# mcu_energy.net
KiCad netlist of a schematic drawn in EAGLE
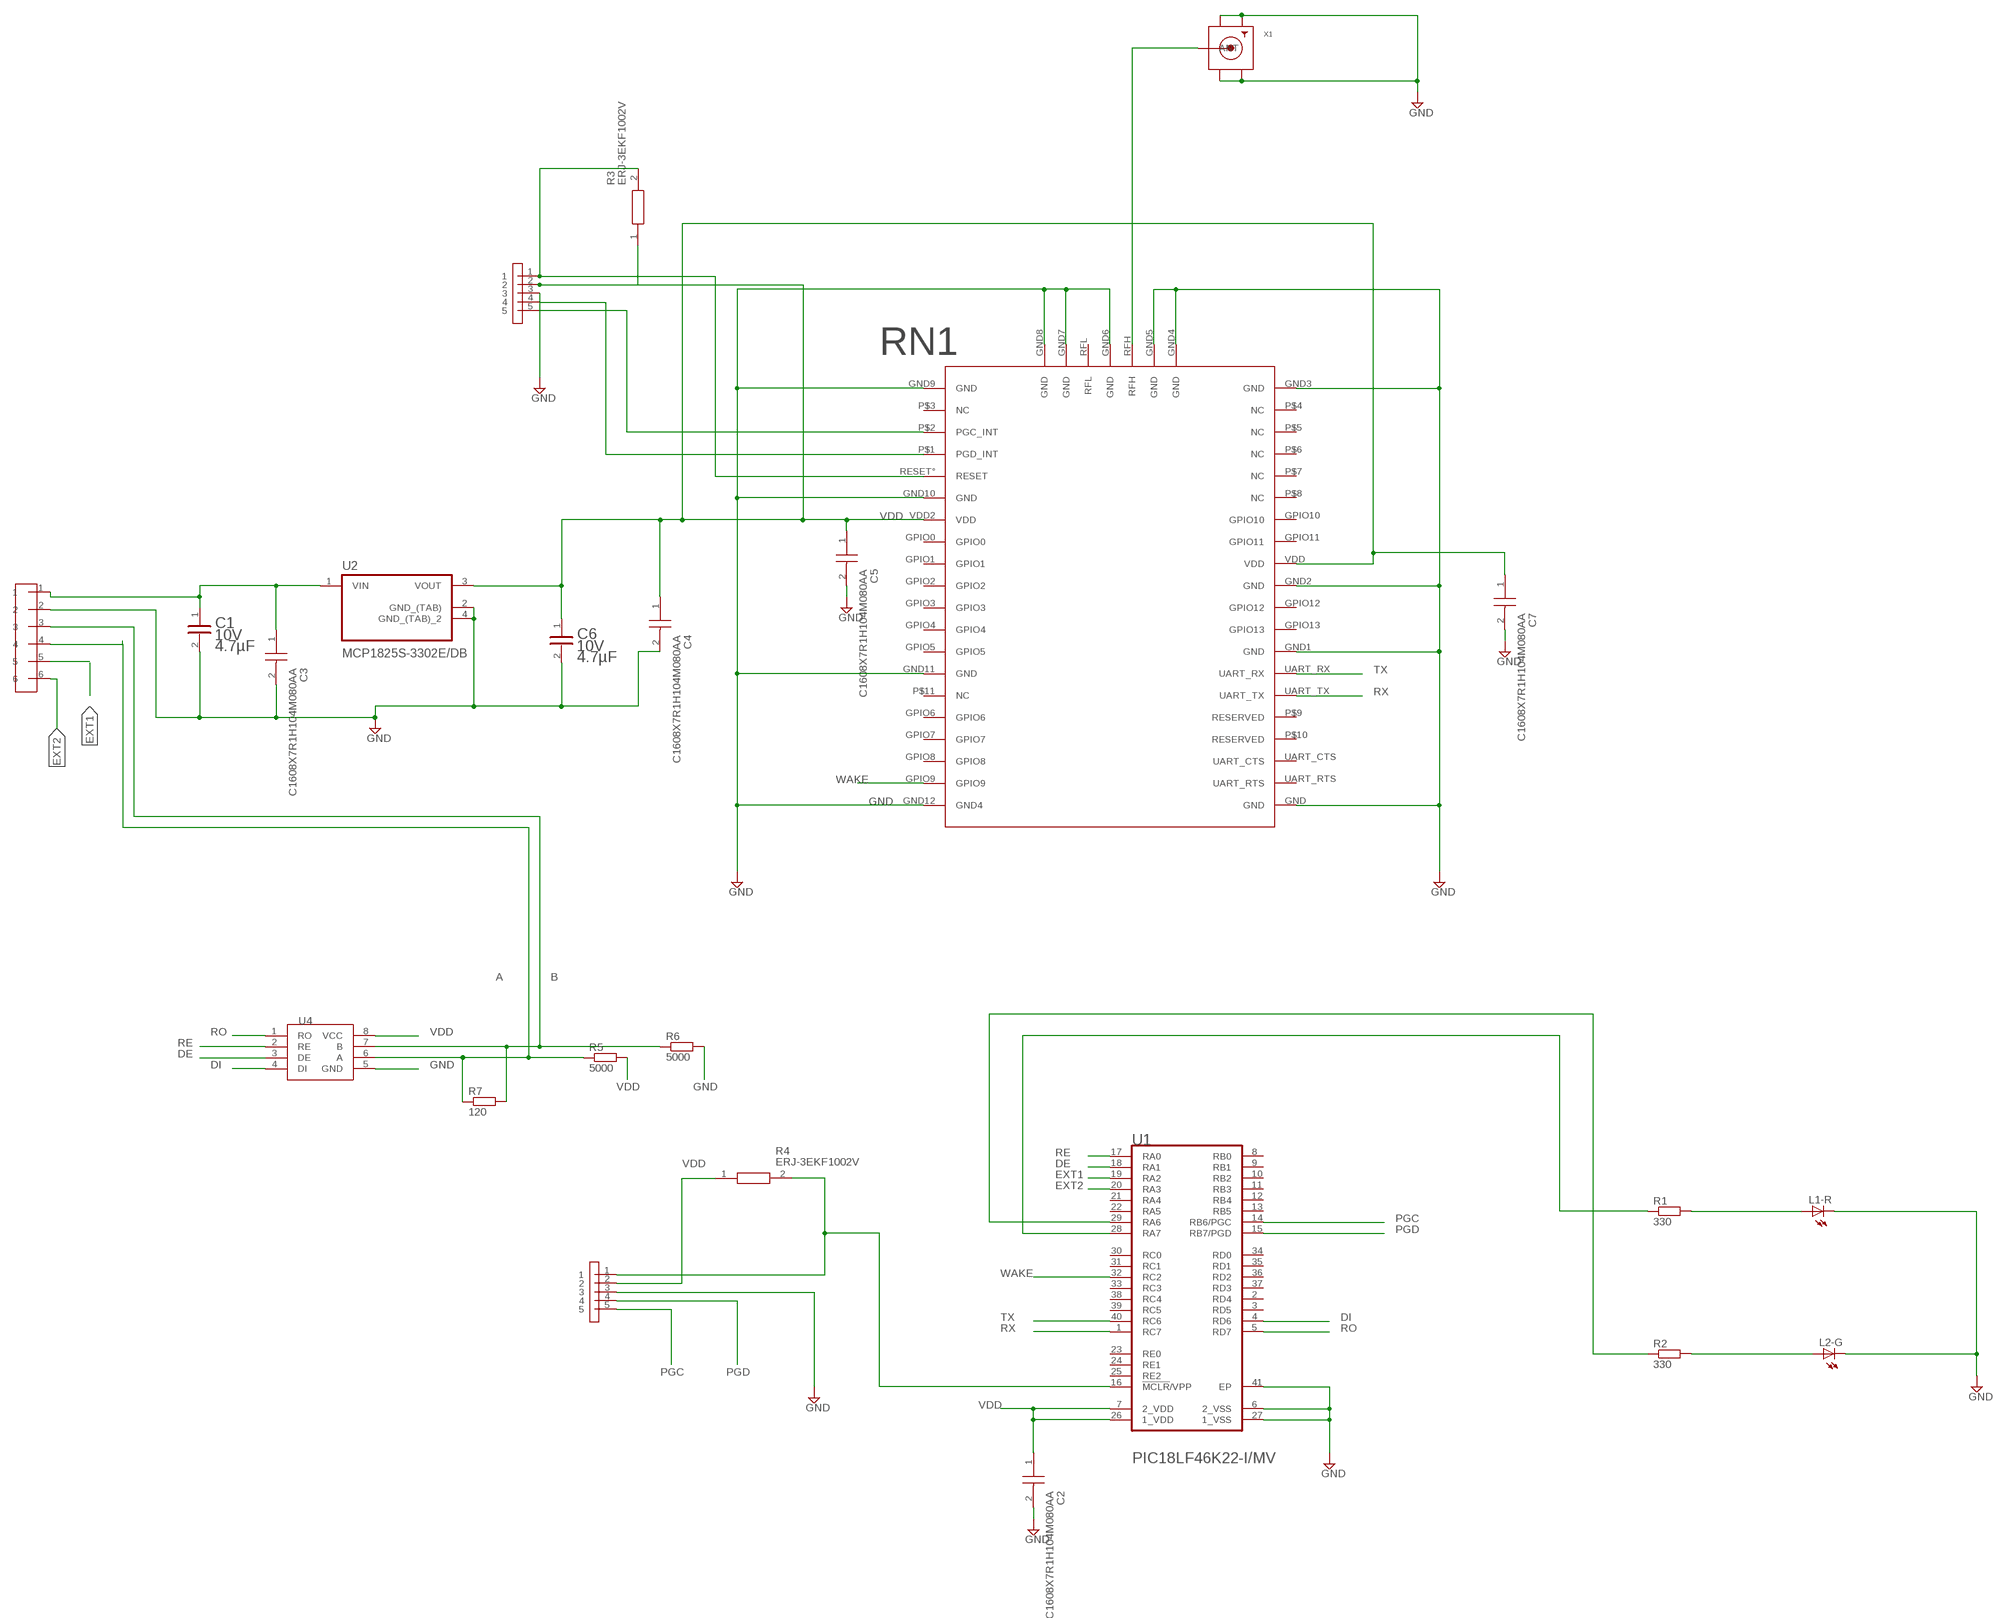
[diagram p0: schematic, sheet 1]

(export (version "E")
  (design (tool "Eeschema 10.0.6"))
  (components
    (comp (ref "C1")
      (value "KEMET_C0603C475K8PACTUKEMET_C0603C475K8PACTU_0_0")
      (footprint "eagle-import:KEMET_C0603C475K8PACTU_0")
      (fields
        (field (name "DIGIKEY_PART_NUMBER") "399-5503-1-ND")
        (field (name "MF") "Kemet")
        (field (name "MOUSER_PART_NUMBER") "80-C0603C475K8P")
      )
      (libsource (lib "eagle-import") (part "KEMET_C0603C475K8PACTUKEMET_C0603C475K8PACTU_0_0"))
    )
    (comp (ref "C2")
      (value "C1608X7R1H104M080AA")
      (footprint "eagle-import:CAPC1608X80N")
      (fields (field (name "MOUSER_PART_NUMBER") "810-C1608X7R1H104M"))
      (libsource (lib "eagle-import") (part "C1608X7R1H104M080AA"))
    )
    (comp (ref "C3")
      (value "C1608X7R1H104M080AA")
      (footprint "eagle-import:CAPC1608X80N")
      (fields (field (name "MOUSER_PART_NUMBER") "810-C1608X7R1H104M"))
      (libsource (lib "eagle-import") (part "C1608X7R1H104M080AA"))
    )
    (comp (ref "C4")
      (value "C1608X7R1H104M080AA")
      (footprint "eagle-import:CAPC1608X80N")
      (fields (field (name "MOUSER_PART_NUMBER") "810-C1608X7R1H104M"))
      (libsource (lib "eagle-import") (part "C1608X7R1H104M080AA"))
    )
    (comp (ref "C5")
      (value "C1608X7R1H104M080AA")
      (footprint "eagle-import:CAPC1608X80N")
      (fields (field (name "MOUSER_PART_NUMBER") "810-C1608X7R1H104M"))
      (libsource (lib "eagle-import") (part "C1608X7R1H104M080AA"))
    )
    (comp (ref "C6")
      (value "KEMET_C0603C475K8PACTUKEMET_C0603C475K8PACTU_0_0")
      (footprint "eagle-import:KEMET_C0603C475K8PACTU_0")
      (fields
        (field (name "DIGIKEY_PART_NUMBER") "399-5503-1-ND")
        (field (name "MF") "Kemet")
        (field (name "MOUSER_PART_NUMBER") "80-C0603C475K8P")
      )
      (libsource (lib "eagle-import") (part "KEMET_C0603C475K8PACTUKEMET_C0603C475K8PACTU_0_0"))
    )
    (comp (ref "C7")
      (value "C1608X7R1H104M080AA")
      (footprint "eagle-import:CAPC1608X80N")
      (fields (field (name "MOUSER_PART_NUMBER") "810-C1608X7R1H104M"))
      (libsource (lib "eagle-import") (part "C1608X7R1H104M080AA"))
    )
    (comp (ref "L1-R")
      (value "LEDCHIP-LED0603")
      (footprint "eagle-import:CHIP-LED0603")
      (libsource (lib "eagle-import") (part "LEDCHIP-LED0603"))
    )
    (comp (ref "L2-G")
      (value "LEDCHIP-LED0603")
      (footprint "eagle-import:CHIP-LED0603")
      (libsource (lib "eagle-import") (part "LEDCHIP-LED0603"))
    )
    (comp (ref "R1")
      (value "330")
      (footprint "eagle-import:R0603")
      (libsource (lib "eagle-import") (part "R-EU_R0603"))
    )
    (comp (ref "R2")
      (value "330")
      (footprint "eagle-import:R0603")
      (libsource (lib "eagle-import") (part "R-EU_R0603"))
    )
    (comp (ref "R3")
      (value "ERJ-3EKF1002V")
      (footprint "eagle-import:RESC1608X55N")
      (fields (field (name "MOUSER_PART_NUMBER") "667-ERJ-3EKF1002V"))
      (libsource (lib "eagle-import") (part "ERJ-3EKF1002V"))
    )
    (comp (ref "R4")
      (value "ERJ-3EKF1002V")
      (footprint "eagle-import:RESC1608X55N")
      (fields (field (name "MOUSER_PART_NUMBER") "667-ERJ-3EKF1002V"))
      (libsource (lib "eagle-import") (part "ERJ-3EKF1002V"))
    )
    (comp (ref "R5")
      (value "5000")
      (footprint "eagle-import:R0805")
      (libsource (lib "eagle-import") (part "rcl_334_R-EU_R0805"))
    )
    (comp (ref "R6")
      (value "5000")
      (footprint "eagle-import:R0805")
      (libsource (lib "eagle-import") (part "rcl_334_R-EU_R0805"))
    )
    (comp (ref "R7")
      (value "120")
      (footprint "eagle-import:R0805")
      (libsource (lib "eagle-import") (part "rcl_334_R-EU_R0805"))
    )
    (comp (ref "RN1")
      (value "NEW_RN2483")
      (footprint "eagle-import:NEW_RN2483")
      (libsource (lib "eagle-import") (part "NEW_RN2483"))
    )
    (comp (ref "U$2")
      (value "ICSP52")
      (footprint "eagle-import:ICSP")
      (libsource (lib "eagle-import") (part "ICSP52"))
    )
    (comp (ref "U$3")
      (value "ICSP_V2")
      (footprint "eagle-import:ICSP_V2")
      (libsource (lib "eagle-import") (part "ICSP_V2"))
    )
    (comp (ref "U1")
      (value "MICROCHIP_PIC18LF46K22-I-MVMICROCHIP_PIC18LF46K22-I-MV_0_1")
      (footprint "eagle-import:MICROCHIP_PIC18LF46K22-I-MV_1")
      (fields (field (name "MF") "Microchip") (field (name "MPN") "PIC18LF46K22-I/MV"))
      (libsource (lib "eagle-import") (part "MICROCHIP_PIC18LF46K22-I-MVMICROCHIP_PIC18LF46K22-I-MV_0_1"))
    )
    (comp (ref "U2")
      (value "MCP1825S-3302E/DB")
      (footprint "eagle-import:SOT230P700X180-4N")
      (fields (field (name "MF") "Microchip"))
      (libsource (lib "eagle-import") (part "MCP1825S-3302E/DB"))
    )
    (comp (ref "U4")
      (value "AMD3485E")
      (footprint "eagle-import:AMD3485E")
      (libsource (lib "eagle-import") (part "AMD3485E"))
    )
    (comp (ref "U6")
      (value "CONNECTOR6_V2")
      (footprint "eagle-import:CONNECTOR6_V2")
      (libsource (lib "eagle-import") (part "CONNECTOR6_V2"))
    )
    (comp (ref "X1")
      (value "SMACONNECTOR_EDGE")
      (footprint "eagle-import:SMA_EDGELAUNCH")
      (libsource (lib "eagle-import") (part "SMACONNECTOR_EDGE"))
    )
  )
  (nets
    (net (code "1") (name "/A") (class "Default")
      (node (ref "R5") (pin "1") (pinfunction "1_1") (pintype "passive"))
      (node (ref "R7") (pin "1") (pinfunction "1_1") (pintype "passive"))
      (node (ref "U4") (pin "6") (pinfunction "A_6") (pintype "bidirectional"))
      (node (ref "U6") (pin "4") (pinfunction "4_4") (pintype "bidirectional"))
    )
    (net (code "2") (name "/B") (class "Default")
      (node (ref "R6") (pin "1") (pinfunction "1_1") (pintype "passive"))
      (node (ref "R7") (pin "2") (pinfunction "2_2") (pintype "passive"))
      (node (ref "U4") (pin "7") (pinfunction "B_7") (pintype "bidirectional"))
      (node (ref "U6") (pin "3") (pinfunction "3_3") (pintype "bidirectional"))
    )
    (net (code "3") (name "/DE") (class "Default")
      (node (ref "U1") (pin "18") (pinfunction "RA1_18") (pintype "bidirectional"))
      (node (ref "U4") (pin "3") (pinfunction "DE_3") (pintype "bidirectional"))
    )
    (net (code "4") (name "/DI") (class "Default")
      (node (ref "U1") (pin "4") (pinfunction "RD6_4") (pintype "bidirectional"))
      (node (ref "U4") (pin "4") (pinfunction "DI_4") (pintype "bidirectional"))
    )
    (net (code "5") (name "/PGC") (class "Default")
      (node (ref "U$2") (pin "5") (pinfunction "5_5") (pintype "bidirectional"))
      (node (ref "U1") (pin "14") (pinfunction "RB6/PGC_14") (pintype "bidirectional"))
    )
    (net (code "6") (name "/PGD") (class "Default")
      (node (ref "U$2") (pin "4") (pinfunction "4_4") (pintype "bidirectional"))
      (node (ref "U1") (pin "15") (pinfunction "RB7/PGD_15") (pintype "bidirectional"))
    )
    (net (code "7") (name "/RE") (class "Default")
      (node (ref "U1") (pin "17") (pinfunction "RA0_17") (pintype "bidirectional"))
      (node (ref "U4") (pin "2") (pinfunction "RE_2") (pintype "bidirectional"))
    )
    (net (code "8") (name "/RO") (class "Default")
      (node (ref "U1") (pin "5") (pinfunction "RD7_5") (pintype "bidirectional"))
      (node (ref "U4") (pin "1") (pinfunction "RO_1") (pintype "bidirectional"))
    )
    (net (code "9") (name "/RX") (class "Default")
      (node (ref "RN1") (pin "UART_TX") (pinfunction "UART_TX_UART_TX") (pintype "bidirectional"))
      (node (ref "U1") (pin "1") (pinfunction "RC7_1") (pintype "bidirectional"))
    )
    (net (code "10") (name "/TX") (class "Default")
      (node (ref "RN1") (pin "UART_RX") (pinfunction "UART_RX_UART_RX") (pintype "bidirectional"))
      (node (ref "U1") (pin "40") (pinfunction "RC6_40") (pintype "bidirectional"))
    )
    (net (code "11") (name "/VDD") (class "Default")
      (node (ref "C2") (pin "1") (pinfunction "1_1") (pintype "bidirectional"))
      (node (ref "C4") (pin "1") (pinfunction "1_1") (pintype "bidirectional"))
      (node (ref "C5") (pin "1") (pinfunction "1_1") (pintype "bidirectional"))
      (node (ref "C6") (pin "1") (pinfunction "1_1") (pintype "bidirectional"))
      (node (ref "C7") (pin "1") (pinfunction "1_1") (pintype "bidirectional"))
      (node (ref "R3") (pin "1") (pinfunction "1_1") (pintype "bidirectional"))
      (node (ref "R4") (pin "1") (pinfunction "1_1") (pintype "bidirectional"))
      (node (ref "R5") (pin "2") (pinfunction "2_2") (pintype "passive"))
      (node (ref "RN1") (pin "VDD") (pinfunction "VDD_VDD") (pintype "bidirectional"))
      (node (ref "RN1") (pin "VDD2") (pinfunction "VDD_VDD2") (pintype "bidirectional"))
      (node (ref "U$2") (pin "2") (pinfunction "2_2") (pintype "bidirectional"))
      (node (ref "U$3") (pin "2") (pinfunction "2_2") (pintype "bidirectional"))
      (node (ref "U1") (pin "26") (pinfunction "1_VDD_26") (pintype "power_in"))
      (node (ref "U1") (pin "7") (pinfunction "2_VDD_7") (pintype "power_in"))
      (node (ref "U2") (pin "3") (pinfunction "VOUT_3") (pintype "output"))
      (node (ref "U4") (pin "8") (pinfunction "VCC_8") (pintype "bidirectional"))
    )
    (net (code "12") (name "/WAKE") (class "Default")
      (node (ref "RN1") (pin "GPIO9") (pinfunction "GPIO9_GPIO9") (pintype "bidirectional"))
      (node (ref "U1") (pin "32") (pinfunction "RC2_32") (pintype "bidirectional"))
    )
    (net (code "13") (name "EXT1") (class "Default")
      (node (ref "U1") (pin "19") (pinfunction "RA2_19") (pintype "bidirectional"))
      (node (ref "U6") (pin "5") (pinfunction "5_5") (pintype "bidirectional"))
    )
    (net (code "14") (name "EXT2") (class "Default")
      (node (ref "U1") (pin "20") (pinfunction "RA3_20") (pintype "bidirectional"))
      (node (ref "U6") (pin "6") (pinfunction "6_6") (pintype "bidirectional"))
    )
    (net (code "15") (name "GND") (class "Default")
      (node (ref "C1") (pin "2") (pinfunction "2_2") (pintype "bidirectional"))
      (node (ref "C2") (pin "2") (pinfunction "2_2") (pintype "bidirectional"))
      (node (ref "C3") (pin "2") (pinfunction "2_2") (pintype "bidirectional"))
      (node (ref "C4") (pin "2") (pinfunction "2_2") (pintype "bidirectional"))
      (node (ref "C5") (pin "2") (pinfunction "2_2") (pintype "bidirectional"))
      (node (ref "C6") (pin "2") (pinfunction "2_2") (pintype "bidirectional"))
      (node (ref "C7") (pin "2") (pinfunction "2_2") (pintype "bidirectional"))
      (node (ref "L1-R") (pin "C") (pinfunction "C_C") (pintype "passive"))
      (node (ref "L2-G") (pin "C") (pinfunction "C_C") (pintype "passive"))
      (node (ref "R6") (pin "2") (pinfunction "2_2") (pintype "passive"))
      (node (ref "RN1") (pin "GND") (pinfunction "GND_GND") (pintype "bidirectional"))
      (node (ref "RN1") (pin "GND1") (pinfunction "GND_GND1") (pintype "bidirectional"))
      (node (ref "RN1") (pin "GND10") (pinfunction "GND_GND10") (pintype "bidirectional"))
      (node (ref "RN1") (pin "GND11") (pinfunction "GND_GND11") (pintype "bidirectional"))
      (node (ref "RN1") (pin "GND12") (pinfunction "GND4_GND12") (pintype "bidirectional"))
      (node (ref "RN1") (pin "GND2") (pinfunction "GND_GND2") (pintype "bidirectional"))
      (node (ref "RN1") (pin "GND3") (pinfunction "GND_GND3") (pintype "bidirectional"))
      (node (ref "RN1") (pin "GND4") (pinfunction "GND_GND4") (pintype "bidirectional"))
      (node (ref "RN1") (pin "GND5") (pinfunction "GND_GND5") (pintype "bidirectional"))
      (node (ref "RN1") (pin "GND6") (pinfunction "GND_GND6") (pintype "bidirectional"))
      (node (ref "RN1") (pin "GND7") (pinfunction "GND_GND7") (pintype "bidirectional"))
      (node (ref "RN1") (pin "GND8") (pinfunction "GND_GND8") (pintype "bidirectional"))
      (node (ref "RN1") (pin "GND9") (pinfunction "GND_GND9") (pintype "bidirectional"))
      (node (ref "U$2") (pin "3") (pinfunction "3_3") (pintype "bidirectional"))
      (node (ref "U$3") (pin "3") (pinfunction "3_3") (pintype "bidirectional"))
      (node (ref "U1") (pin "27") (pinfunction "1_VSS_27") (pintype "power_in"))
      (node (ref "U1") (pin "41") (pinfunction "EP_41") (pintype "passive"))
      (node (ref "U1") (pin "6") (pinfunction "2_VSS_6") (pintype "power_in"))
      (node (ref "U2") (pin "2") (pinfunction "GND_(TAB)_2") (pintype "power_in"))
      (node (ref "U2") (pin "4") (pinfunction "GND_(TAB)_2_4") (pintype "power_in"))
      (node (ref "U4") (pin "5") (pinfunction "GND_5") (pintype "bidirectional"))
      (node (ref "U6") (pin "2") (pinfunction "2_2") (pintype "bidirectional"))
      (node (ref "X1") (pin "GND@1") (pinfunction "GND4_GND@1") (pintype "power_in"))
      (node (ref "X1") (pin "GND@2") (pinfunction "GND3_GND@2") (pintype "power_in"))
      (node (ref "X1") (pin "GND@3") (pinfunction "GND2_GND@3") (pintype "power_in"))
      (node (ref "X1") (pin "GND@4") (pinfunction "GND1_GND@4") (pintype "power_in"))
    )
    (net (code "16") (name "Net-(L1-R-PadA)") (class "Default")
      (node (ref "L1-R") (pin "A") (pinfunction "A_A") (pintype "passive"))
      (node (ref "R1") (pin "2") (pinfunction "2_2") (pintype "passive"))
    )
    (net (code "17") (name "Net-(L2-G-PadA)") (class "Default")
      (node (ref "L2-G") (pin "A") (pinfunction "A_A") (pintype "passive"))
      (node (ref "R2") (pin "2") (pinfunction "2_2") (pintype "passive"))
    )
    (net (code "18") (name "Net-(RN1-PGC_INT)") (class "Default")
      (node (ref "RN1") (pin "P$2") (pinfunction "PGC_INT_P$2") (pintype "bidirectional"))
      (node (ref "U$3") (pin "5") (pinfunction "5_5") (pintype "bidirectional"))
    )
    (net (code "19") (name "Net-(RN1-PGD_INT)") (class "Default")
      (node (ref "RN1") (pin "P$1") (pinfunction "PGD_INT_P$1") (pintype "bidirectional"))
      (node (ref "U$3") (pin "4") (pinfunction "4_4") (pintype "bidirectional"))
    )
    (net (code "20") (name "Net-(RN1-RESET)") (class "Default")
      (node (ref "R3") (pin "2") (pinfunction "2_2") (pintype "bidirectional"))
      (node (ref "RN1") (pin "RESET°") (pinfunction "RESET_RESET°") (pintype "bidirectional"))
      (node (ref "U$3") (pin "1") (pinfunction "1_1") (pintype "bidirectional"))
    )
    (net (code "21") (name "Net-(U1-RA6)") (class "Default")
      (node (ref "R2") (pin "1") (pinfunction "1_1") (pintype "passive"))
      (node (ref "U1") (pin "29") (pinfunction "RA6_29") (pintype "bidirectional"))
    )
    (net (code "22") (name "Net-(U1-RA7)") (class "Default")
      (node (ref "R1") (pin "1") (pinfunction "1_1") (pintype "passive"))
      (node (ref "U1") (pin "28") (pinfunction "RA7_28") (pintype "bidirectional"))
    )
    (net (code "23") (name "Net-(U1-~{MCLR}{slash}VPP)") (class "Default")
      (node (ref "R4") (pin "2") (pinfunction "2_2") (pintype "bidirectional"))
      (node (ref "U$2") (pin "1") (pinfunction "1_1") (pintype "bidirectional"))
      (node (ref "U1") (pin "16") (pinfunction "~{MCLR}/VPP_16") (pintype "input"))
    )
    (net (code "24") (name "Net-(U2-VIN)") (class "Default")
      (node (ref "C1") (pin "1") (pinfunction "1_1") (pintype "bidirectional"))
      (node (ref "C3") (pin "1") (pinfunction "1_1") (pintype "bidirectional"))
      (node (ref "U2") (pin "1") (pinfunction "VIN_1") (pintype "input"))
      (node (ref "U6") (pin "1") (pinfunction "1_1") (pintype "bidirectional"))
    )
    (net (code "25") (name "Net-(X1-ANT)") (class "Default")
      (node (ref "RN1") (pin "RFH") (pinfunction "RFH_RFH") (pintype "bidirectional"))
      (node (ref "X1") (pin "P") (pinfunction "ANT_P") (pintype "bidirectional"))
    )
    (net (code "26") (name "unconnected-(RN1-NC-PadP$3)") (class "Default")
      (node (ref "RN1") (pin "P$3") (pinfunction "NC_P$3") (pintype "bidirectional"))
    )
    (net (code "27") (name "unconnected-(RN1-NC-PadP$4)") (class "Default")
      (node (ref "RN1") (pin "P$4") (pinfunction "NC_P$4") (pintype "bidirectional"))
    )
    (net (code "28") (name "unconnected-(RN1-NC-PadP$5)") (class "Default")
      (node (ref "RN1") (pin "P$5") (pinfunction "NC_P$5") (pintype "bidirectional"))
    )
    (net (code "29") (name "unconnected-(RN1-NC-PadP$6)") (class "Default")
      (node (ref "RN1") (pin "P$6") (pinfunction "NC_P$6") (pintype "bidirectional"))
    )
    (net (code "30") (name "unconnected-(RN1-NC-PadP$7)") (class "Default")
      (node (ref "RN1") (pin "P$7") (pinfunction "NC_P$7") (pintype "bidirectional"))
    )
    (net (code "31") (name "unconnected-(RN1-NC-PadP$8)") (class "Default")
      (node (ref "RN1") (pin "P$8") (pinfunction "NC_P$8") (pintype "bidirectional"))
    )
    (net (code "32") (name "unconnected-(RN1-NC-PadP$11)") (class "Default")
      (node (ref "RN1") (pin "P$11") (pinfunction "NC_P$11") (pintype "bidirectional"))
    )
    (net (code "33") (name "unconnected-(RN1-PadGPIO0)") (class "Default")
      (node (ref "RN1") (pin "GPIO0") (pinfunction "GPIO0_GPIO0") (pintype "bidirectional"))
    )
    (net (code "34") (name "unconnected-(RN1-PadGPIO1)") (class "Default")
      (node (ref "RN1") (pin "GPIO1") (pinfunction "GPIO1_GPIO1") (pintype "bidirectional"))
    )
    (net (code "35") (name "unconnected-(RN1-PadGPIO2)") (class "Default")
      (node (ref "RN1") (pin "GPIO2") (pinfunction "GPIO2_GPIO2") (pintype "bidirectional"))
    )
    (net (code "36") (name "unconnected-(RN1-PadGPIO3)") (class "Default")
      (node (ref "RN1") (pin "GPIO3") (pinfunction "GPIO3_GPIO3") (pintype "bidirectional"))
    )
    (net (code "37") (name "unconnected-(RN1-PadGPIO4)") (class "Default")
      (node (ref "RN1") (pin "GPIO4") (pinfunction "GPIO4_GPIO4") (pintype "bidirectional"))
    )
    (net (code "38") (name "unconnected-(RN1-PadGPIO5)") (class "Default")
      (node (ref "RN1") (pin "GPIO5") (pinfunction "GPIO5_GPIO5") (pintype "bidirectional"))
    )
    (net (code "39") (name "unconnected-(RN1-PadGPIO6)") (class "Default")
      (node (ref "RN1") (pin "GPIO6") (pinfunction "GPIO6_GPIO6") (pintype "bidirectional"))
    )
    (net (code "40") (name "unconnected-(RN1-PadGPIO7)") (class "Default")
      (node (ref "RN1") (pin "GPIO7") (pinfunction "GPIO7_GPIO7") (pintype "bidirectional"))
    )
    (net (code "41") (name "unconnected-(RN1-PadGPIO8)") (class "Default")
      (node (ref "RN1") (pin "GPIO8") (pinfunction "GPIO8_GPIO8") (pintype "bidirectional"))
    )
    (net (code "42") (name "unconnected-(RN1-PadGPIO10)") (class "Default")
      (node (ref "RN1") (pin "GPIO10") (pinfunction "GPIO10_GPIO10") (pintype "bidirectional"))
    )
    (net (code "43") (name "unconnected-(RN1-PadGPIO11)") (class "Default")
      (node (ref "RN1") (pin "GPIO11") (pinfunction "GPIO11_GPIO11") (pintype "bidirectional"))
    )
    (net (code "44") (name "unconnected-(RN1-PadGPIO12)") (class "Default")
      (node (ref "RN1") (pin "GPIO12") (pinfunction "GPIO12_GPIO12") (pintype "bidirectional"))
    )
    (net (code "45") (name "unconnected-(RN1-PadGPIO13)") (class "Default")
      (node (ref "RN1") (pin "GPIO13") (pinfunction "GPIO13_GPIO13") (pintype "bidirectional"))
    )
    (net (code "46") (name "unconnected-(RN1-PadRFL)") (class "Default")
      (node (ref "RN1") (pin "RFL") (pinfunction "RFL_RFL") (pintype "bidirectional"))
    )
    (net (code "47") (name "unconnected-(RN1-PadUART_CTS)") (class "Default")
      (node (ref "RN1") (pin "UART_CTS") (pinfunction "UART_CTS_UART_CTS") (pintype "bidirectional"))
    )
    (net (code "48") (name "unconnected-(RN1-PadUART_RTS)") (class "Default")
      (node (ref "RN1") (pin "UART_RTS") (pinfunction "UART_RTS_UART_RTS") (pintype "bidirectional"))
    )
    (net (code "49") (name "unconnected-(RN1-RESERVED-PadP$9)") (class "Default")
      (node (ref "RN1") (pin "P$9") (pinfunction "RESERVED_P$9") (pintype "bidirectional"))
    )
    (net (code "50") (name "unconnected-(RN1-RESERVED-PadP$10)") (class "Default")
      (node (ref "RN1") (pin "P$10") (pinfunction "RESERVED_P$10") (pintype "bidirectional"))
    )
    (net (code "51") (name "unconnected-(U1-RA4-Pad21)") (class "Default")
      (node (ref "U1") (pin "21") (pinfunction "RA4_21") (pintype "bidirectional"))
    )
    (net (code "52") (name "unconnected-(U1-RA5-Pad22)") (class "Default")
      (node (ref "U1") (pin "22") (pinfunction "RA5_22") (pintype "bidirectional"))
    )
    (net (code "53") (name "unconnected-(U1-RB0-Pad8)") (class "Default")
      (node (ref "U1") (pin "8") (pinfunction "RB0_8") (pintype "bidirectional"))
    )
    (net (code "54") (name "unconnected-(U1-RB1-Pad9)") (class "Default")
      (node (ref "U1") (pin "9") (pinfunction "RB1_9") (pintype "bidirectional"))
    )
    (net (code "55") (name "unconnected-(U1-RB2-Pad10)") (class "Default")
      (node (ref "U1") (pin "10") (pinfunction "RB2_10") (pintype "bidirectional"))
    )
    (net (code "56") (name "unconnected-(U1-RB3-Pad11)") (class "Default")
      (node (ref "U1") (pin "11") (pinfunction "RB3_11") (pintype "bidirectional"))
    )
    (net (code "57") (name "unconnected-(U1-RB4-Pad12)") (class "Default")
      (node (ref "U1") (pin "12") (pinfunction "RB4_12") (pintype "bidirectional"))
    )
    (net (code "58") (name "unconnected-(U1-RB5-Pad13)") (class "Default")
      (node (ref "U1") (pin "13") (pinfunction "RB5_13") (pintype "bidirectional"))
    )
    (net (code "59") (name "unconnected-(U1-RC0-Pad30)") (class "Default")
      (node (ref "U1") (pin "30") (pinfunction "RC0_30") (pintype "bidirectional"))
    )
    (net (code "60") (name "unconnected-(U1-RC1-Pad31)") (class "Default")
      (node (ref "U1") (pin "31") (pinfunction "RC1_31") (pintype "bidirectional"))
    )
    (net (code "61") (name "unconnected-(U1-RC3-Pad33)") (class "Default")
      (node (ref "U1") (pin "33") (pinfunction "RC3_33") (pintype "bidirectional"))
    )
    (net (code "62") (name "unconnected-(U1-RC4-Pad38)") (class "Default")
      (node (ref "U1") (pin "38") (pinfunction "RC4_38") (pintype "bidirectional"))
    )
    (net (code "63") (name "unconnected-(U1-RC5-Pad39)") (class "Default")
      (node (ref "U1") (pin "39") (pinfunction "RC5_39") (pintype "bidirectional"))
    )
    (net (code "64") (name "unconnected-(U1-RD0-Pad34)") (class "Default")
      (node (ref "U1") (pin "34") (pinfunction "RD0_34") (pintype "bidirectional"))
    )
    (net (code "65") (name "unconnected-(U1-RD1-Pad35)") (class "Default")
      (node (ref "U1") (pin "35") (pinfunction "RD1_35") (pintype "bidirectional"))
    )
    (net (code "66") (name "unconnected-(U1-RD2-Pad36)") (class "Default")
      (node (ref "U1") (pin "36") (pinfunction "RD2_36") (pintype "bidirectional"))
    )
    (net (code "67") (name "unconnected-(U1-RD3-Pad37)") (class "Default")
      (node (ref "U1") (pin "37") (pinfunction "RD3_37") (pintype "bidirectional"))
    )
    (net (code "68") (name "unconnected-(U1-RD4-Pad2)") (class "Default")
      (node (ref "U1") (pin "2") (pinfunction "RD4_2") (pintype "bidirectional"))
    )
    (net (code "69") (name "unconnected-(U1-RD5-Pad3)") (class "Default")
      (node (ref "U1") (pin "3") (pinfunction "RD5_3") (pintype "bidirectional"))
    )
    (net (code "70") (name "unconnected-(U1-RE0-Pad23)") (class "Default")
      (node (ref "U1") (pin "23") (pinfunction "RE0_23") (pintype "bidirectional"))
    )
    (net (code "71") (name "unconnected-(U1-RE1-Pad24)") (class "Default")
      (node (ref "U1") (pin "24") (pinfunction "RE1_24") (pintype "bidirectional"))
    )
    (net (code "72") (name "unconnected-(U1-RE2-Pad25)") (class "Default")
      (node (ref "U1") (pin "25") (pinfunction "RE2_25") (pintype "bidirectional"))
    )
  )
)
